# MotorBoardPrototyp4_ptcfuse.net
KiCad netlist of a schematic drawn in EAGLE
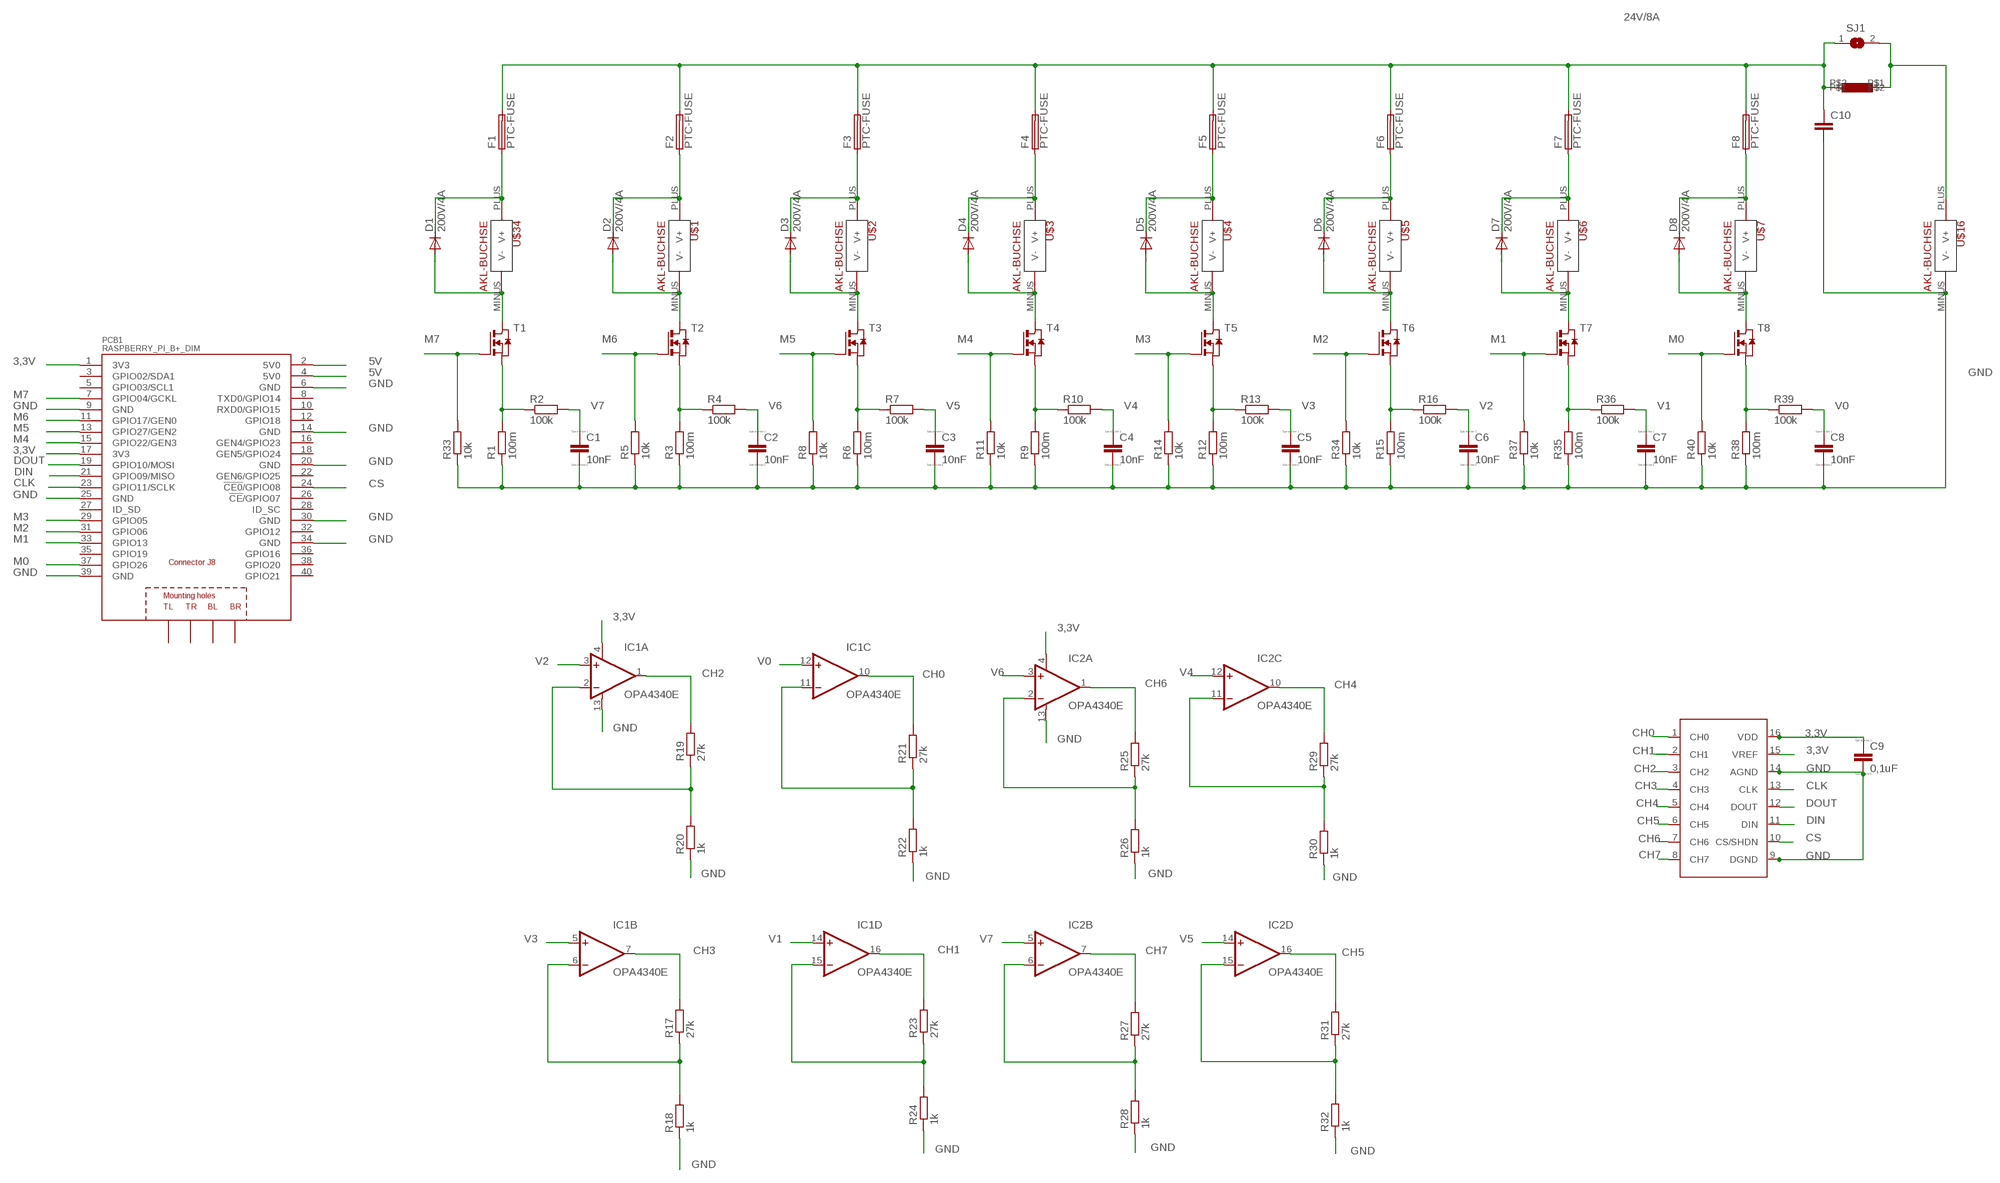
[diagram p0: schematic, sheet 1]

(export (version "E")
  (design (tool "Eeschema 10.0.6"))
  (components
    (comp (ref "C1")
      (value "10nF")
      (footprint "eagle-import:C0805")
      (libsource (lib "eagle-import") (part "C"))
    )
    (comp (ref "C2")
      (value "10nF")
      (footprint "eagle-import:C0805")
      (libsource (lib "eagle-import") (part "C"))
    )
    (comp (ref "C3")
      (value "10nF")
      (footprint "eagle-import:C0805")
      (libsource (lib "eagle-import") (part "C"))
    )
    (comp (ref "C4")
      (value "10nF")
      (footprint "eagle-import:C0805")
      (libsource (lib "eagle-import") (part "C"))
    )
    (comp (ref "C5")
      (value "10nF")
      (footprint "eagle-import:C0805")
      (libsource (lib "eagle-import") (part "C"))
    )
    (comp (ref "C6")
      (value "10nF")
      (footprint "eagle-import:C0805")
      (libsource (lib "eagle-import") (part "C"))
    )
    (comp (ref "C7")
      (value "10nF")
      (footprint "eagle-import:C0805")
      (libsource (lib "eagle-import") (part "C"))
    )
    (comp (ref "C8")
      (value "10nF")
      (footprint "eagle-import:C0805")
      (libsource (lib "eagle-import") (part "C"))
    )
    (comp (ref "C9")
      (value "0,1uF")
      (footprint "eagle-import:C0805")
      (libsource (lib "eagle-import") (part "C"))
    )
    (comp (ref "C10")
      (value "C-EUC1812")
      (footprint "eagle-import:C1812")
      (libsource (lib "eagle-import") (part "C-EUC1812"))
    )
    (comp (ref "D1")
      (value "200V/4A")
      (footprint "eagle-import:DO214AA")
      (libsource (lib "eagle-import") (part "DIODE-DO214AA"))
    )
    (comp (ref "D2")
      (value "200V/4A")
      (footprint "eagle-import:DO214AA")
      (libsource (lib "eagle-import") (part "DIODE-DO214AA"))
    )
    (comp (ref "D3")
      (value "200V/4A")
      (footprint "eagle-import:DO214AA")
      (libsource (lib "eagle-import") (part "DIODE-DO214AA"))
    )
    (comp (ref "D4")
      (value "200V/4A")
      (footprint "eagle-import:DO214AA")
      (libsource (lib "eagle-import") (part "DIODE-DO214AA"))
    )
    (comp (ref "D5")
      (value "200V/4A")
      (footprint "eagle-import:DO214AA")
      (libsource (lib "eagle-import") (part "DIODE-DO214AA"))
    )
    (comp (ref "D6")
      (value "200V/4A")
      (footprint "eagle-import:DO214AA")
      (libsource (lib "eagle-import") (part "DIODE-DO214AA"))
    )
    (comp (ref "D7")
      (value "200V/4A")
      (footprint "eagle-import:DO214AA")
      (libsource (lib "eagle-import") (part "DIODE-DO214AA"))
    )
    (comp (ref "D8")
      (value "200V/4A")
      (footprint "eagle-import:DO214AA")
      (libsource (lib "eagle-import") (part "DIODE-DO214AA"))
    )
    (comp (ref "F1")
      (value "PTC-FUSE")
      (footprint "eagle-import:SMDF050")
      (libsource (lib "eagle-import") (part "PTC-FUSE"))
    )
    (comp (ref "F2")
      (value "PTC-FUSE")
      (footprint "eagle-import:SMDF050")
      (libsource (lib "eagle-import") (part "PTC-FUSE"))
    )
    (comp (ref "F3")
      (value "PTC-FUSE")
      (footprint "eagle-import:SMDF050")
      (libsource (lib "eagle-import") (part "PTC-FUSE"))
    )
    (comp (ref "F4")
      (value "PTC-FUSE")
      (footprint "eagle-import:SMDF050")
      (libsource (lib "eagle-import") (part "PTC-FUSE"))
    )
    (comp (ref "F5")
      (value "PTC-FUSE")
      (footprint "eagle-import:SMDF050")
      (libsource (lib "eagle-import") (part "PTC-FUSE"))
    )
    (comp (ref "F6")
      (value "PTC-FUSE")
      (footprint "eagle-import:SMDF050")
      (libsource (lib "eagle-import") (part "PTC-FUSE"))
    )
    (comp (ref "F7")
      (value "PTC-FUSE")
      (footprint "eagle-import:SMDF050")
      (libsource (lib "eagle-import") (part "PTC-FUSE"))
    )
    (comp (ref "F8")
      (value "PTC-FUSE")
      (footprint "eagle-import:SMDF050")
      (libsource (lib "eagle-import") (part "PTC-FUSE"))
    )
    (comp (ref "IC1")
      (value "OPA4340E")
      (footprint "eagle-import:SSOP16BU")
      (fields (field (name "MPN") "OPA4340EA/250G4"))
      (libsource (lib "eagle-import") (part "OPA4340E"))
    )
    (comp (ref "IC2")
      (value "OPA4340E")
      (footprint "eagle-import:SSOP16BU")
      (fields (field (name "MPN") "OPA4340EA/250G4"))
      (libsource (lib "eagle-import") (part "OPA4340E"))
    )
    (comp (ref "L1")
      (value "MPI4040")
      (footprint "eagle-import:4040")
      (libsource (lib "eagle-import") (part "MPI4040"))
    )
    (comp (ref "PCB1")
      (value "RASPBERRY_PI_B+_DIM")
      (footprint "eagle-import:RASPBERRY_PI_BPLUS_DIM")
      (libsource (lib "eagle-import") (part "RASPBERRY_PI_B+_DIM"))
    )
    (comp (ref "R1")
      (value "100m")
      (footprint "eagle-import:R0805")
      (libsource (lib "eagle-import") (part "R-EU_R0805"))
    )
    (comp (ref "R2")
      (value "100k")
      (footprint "eagle-import:R0805")
      (libsource (lib "eagle-import") (part "R-EU_R0805"))
    )
    (comp (ref "R3")
      (value "100m")
      (footprint "eagle-import:R0805")
      (libsource (lib "eagle-import") (part "R-EU_R0805"))
    )
    (comp (ref "R4")
      (value "100k")
      (footprint "eagle-import:R0805")
      (libsource (lib "eagle-import") (part "R-EU_R0805"))
    )
    (comp (ref "R5")
      (value "10k")
      (footprint "eagle-import:R0805")
      (libsource (lib "eagle-import") (part "R-EU_R0805"))
    )
    (comp (ref "R6")
      (value "100m")
      (footprint "eagle-import:R0805")
      (libsource (lib "eagle-import") (part "R-EU_R0805"))
    )
    (comp (ref "R7")
      (value "100k")
      (footprint "eagle-import:R0805")
      (libsource (lib "eagle-import") (part "R-EU_R0805"))
    )
    (comp (ref "R8")
      (value "10k")
      (footprint "eagle-import:R0805")
      (libsource (lib "eagle-import") (part "R-EU_R0805"))
    )
    (comp (ref "R9")
      (value "100m")
      (footprint "eagle-import:R0805")
      (libsource (lib "eagle-import") (part "R-EU_R0805"))
    )
    (comp (ref "R10")
      (value "100k")
      (footprint "eagle-import:R0805")
      (libsource (lib "eagle-import") (part "R-EU_R0805"))
    )
    (comp (ref "R11")
      (value "10k")
      (footprint "eagle-import:R0805")
      (libsource (lib "eagle-import") (part "R-EU_R0805"))
    )
    (comp (ref "R12")
      (value "100m")
      (footprint "eagle-import:R0805")
      (libsource (lib "eagle-import") (part "R-EU_R0805"))
    )
    (comp (ref "R13")
      (value "100k")
      (footprint "eagle-import:R0805")
      (libsource (lib "eagle-import") (part "R-EU_R0805"))
    )
    (comp (ref "R14")
      (value "10k")
      (footprint "eagle-import:R0805")
      (libsource (lib "eagle-import") (part "R-EU_R0805"))
    )
    (comp (ref "R15")
      (value "100m")
      (footprint "eagle-import:R0805")
      (libsource (lib "eagle-import") (part "R-EU_R0805"))
    )
    (comp (ref "R16")
      (value "100k")
      (footprint "eagle-import:R0805")
      (libsource (lib "eagle-import") (part "R-EU_R0805"))
    )
    (comp (ref "R17")
      (value "27k")
      (footprint "eagle-import:R0805")
      (libsource (lib "eagle-import") (part "R-EU_R0805"))
    )
    (comp (ref "R18")
      (value "1k")
      (footprint "eagle-import:R0805")
      (libsource (lib "eagle-import") (part "R-EU_R0805"))
    )
    (comp (ref "R19")
      (value "27k")
      (footprint "eagle-import:R0805")
      (libsource (lib "eagle-import") (part "R-EU_R0805"))
    )
    (comp (ref "R20")
      (value "1k")
      (footprint "eagle-import:R0805")
      (libsource (lib "eagle-import") (part "R-EU_R0805"))
    )
    (comp (ref "R21")
      (value "27k")
      (footprint "eagle-import:R0805")
      (libsource (lib "eagle-import") (part "R-EU_R0805"))
    )
    (comp (ref "R22")
      (value "1k")
      (footprint "eagle-import:R0805")
      (libsource (lib "eagle-import") (part "R-EU_R0805"))
    )
    (comp (ref "R23")
      (value "27k")
      (footprint "eagle-import:R0805")
      (libsource (lib "eagle-import") (part "R-EU_R0805"))
    )
    (comp (ref "R24")
      (value "1k")
      (footprint "eagle-import:R0805")
      (libsource (lib "eagle-import") (part "R-EU_R0805"))
    )
    (comp (ref "R25")
      (value "27k")
      (footprint "eagle-import:R0805")
      (libsource (lib "eagle-import") (part "R-EU_R0805"))
    )
    (comp (ref "R26")
      (value "1k")
      (footprint "eagle-import:R0805")
      (libsource (lib "eagle-import") (part "R-EU_R0805"))
    )
    (comp (ref "R27")
      (value "27k")
      (footprint "eagle-import:R0805")
      (libsource (lib "eagle-import") (part "R-EU_R0805"))
    )
    (comp (ref "R28")
      (value "1k")
      (footprint "eagle-import:R0805")
      (libsource (lib "eagle-import") (part "R-EU_R0805"))
    )
    (comp (ref "R29")
      (value "27k")
      (footprint "eagle-import:R0805")
      (libsource (lib "eagle-import") (part "R-EU_R0805"))
    )
    (comp (ref "R30")
      (value "1k")
      (footprint "eagle-import:R0805")
      (libsource (lib "eagle-import") (part "R-EU_R0805"))
    )
    (comp (ref "R31")
      (value "27k")
      (footprint "eagle-import:R0805")
      (libsource (lib "eagle-import") (part "R-EU_R0805"))
    )
    (comp (ref "R32")
      (value "1k")
      (footprint "eagle-import:R0805")
      (libsource (lib "eagle-import") (part "R-EU_R0805"))
    )
    (comp (ref "R33")
      (value "10k")
      (footprint "eagle-import:R0805")
      (libsource (lib "eagle-import") (part "R-EU_R0805"))
    )
    (comp (ref "R34")
      (value "10k")
      (footprint "eagle-import:R0805")
      (libsource (lib "eagle-import") (part "R-EU_R0805"))
    )
    (comp (ref "R35")
      (value "100m")
      (footprint "eagle-import:R0805")
      (libsource (lib "eagle-import") (part "R-EU_R0805"))
    )
    (comp (ref "R36")
      (value "100k")
      (footprint "eagle-import:R0805")
      (libsource (lib "eagle-import") (part "R-EU_R0805"))
    )
    (comp (ref "R37")
      (value "10k")
      (footprint "eagle-import:R0805")
      (libsource (lib "eagle-import") (part "R-EU_R0805"))
    )
    (comp (ref "R38")
      (value "100m")
      (footprint "eagle-import:R0805")
      (libsource (lib "eagle-import") (part "R-EU_R0805"))
    )
    (comp (ref "R39")
      (value "100k")
      (footprint "eagle-import:R0805")
      (libsource (lib "eagle-import") (part "R-EU_R0805"))
    )
    (comp (ref "R40")
      (value "10k")
      (footprint "eagle-import:R0805")
      (libsource (lib "eagle-import") (part "R-EU_R0805"))
    )
    (comp (ref "SJ1") (value "SJ") (footprint "eagle-import:SJ") (libsource (lib "eagle-import") (part "SJ")))
    (comp (ref "T1")
      (value "NMOSSOT23")
      (footprint "eagle-import:SOT-23")
      (libsource (lib "eagle-import") (part "NMOSSOT23"))
    )
    (comp (ref "T2")
      (value "NMOSSOT23")
      (footprint "eagle-import:SOT-23")
      (libsource (lib "eagle-import") (part "NMOSSOT23"))
    )
    (comp (ref "T3")
      (value "NMOSSOT23")
      (footprint "eagle-import:SOT-23")
      (libsource (lib "eagle-import") (part "NMOSSOT23"))
    )
    (comp (ref "T4")
      (value "NMOSSOT23")
      (footprint "eagle-import:SOT-23")
      (libsource (lib "eagle-import") (part "NMOSSOT23"))
    )
    (comp (ref "T5")
      (value "NMOSSOT23")
      (footprint "eagle-import:SOT-23")
      (libsource (lib "eagle-import") (part "NMOSSOT23"))
    )
    (comp (ref "T6")
      (value "NMOSSOT23")
      (footprint "eagle-import:SOT-23")
      (libsource (lib "eagle-import") (part "NMOSSOT23"))
    )
    (comp (ref "T7")
      (value "NMOSSOT23")
      (footprint "eagle-import:SOT-23")
      (libsource (lib "eagle-import") (part "NMOSSOT23"))
    )
    (comp (ref "T8")
      (value "NMOSSOT23")
      (footprint "eagle-import:SOT-23")
      (libsource (lib "eagle-import") (part "NMOSSOT23"))
    )
    (comp (ref "U$1")
      (value "AKL-BUCHSE")
      (footprint "eagle-import:AKL-BUCHSE")
      (libsource (lib "eagle-import") (part "AKL-BUCHSE"))
    )
    (comp (ref "U$2")
      (value "AKL-BUCHSE")
      (footprint "eagle-import:AKL-BUCHSE")
      (libsource (lib "eagle-import") (part "AKL-BUCHSE"))
    )
    (comp (ref "U$3")
      (value "AKL-BUCHSE")
      (footprint "eagle-import:AKL-BUCHSE")
      (libsource (lib "eagle-import") (part "AKL-BUCHSE"))
    )
    (comp (ref "U$4")
      (value "AKL-BUCHSE")
      (footprint "eagle-import:AKL-BUCHSE")
      (libsource (lib "eagle-import") (part "AKL-BUCHSE"))
    )
    (comp (ref "U$5")
      (value "AKL-BUCHSE")
      (footprint "eagle-import:AKL-BUCHSE")
      (libsource (lib "eagle-import") (part "AKL-BUCHSE"))
    )
    (comp (ref "U$6")
      (value "AKL-BUCHSE")
      (footprint "eagle-import:AKL-BUCHSE")
      (libsource (lib "eagle-import") (part "AKL-BUCHSE"))
    )
    (comp (ref "U$7")
      (value "AKL-BUCHSE")
      (footprint "eagle-import:AKL-BUCHSE")
      (libsource (lib "eagle-import") (part "AKL-BUCHSE"))
    )
    (comp (ref "U$16")
      (value "AKL-BUCHSE")
      (footprint "eagle-import:AKL-BUCHSE")
      (libsource (lib "eagle-import") (part "AKL-BUCHSE"))
    )
    (comp (ref "U$34")
      (value "AKL-BUCHSE")
      (footprint "eagle-import:AKL-BUCHSE")
      (libsource (lib "eagle-import") (part "AKL-BUCHSE"))
    )
    (comp (ref "U$58")
      (value "MCP3008SO16")
      (footprint "eagle-import:SO16")
      (libsource (lib "eagle-import") (part "MCP3008SO16"))
    )
  )
  (nets
    (net (code "1") (name "/3,3V") (class "Default")
      (node (ref "C9") (pin "1") (pinfunction "1_1") (pintype "passive"))
      (node (ref "IC1") (pin "4") (pinfunction "V+_4") (pintype "power_in"))
      (node (ref "IC2") (pin "4") (pinfunction "V+_4") (pintype "power_in"))
      (node (ref "PCB1") (pin "1") (pinfunction "3V3_1") (pintype "power_in"))
      (node (ref "PCB1") (pin "17") (pinfunction "3V3_17") (pintype "power_in"))
      (node (ref "U$58") (pin "15") (pinfunction "VREF_15") (pintype "bidirectional"))
      (node (ref "U$58") (pin "16") (pinfunction "VDD_16") (pintype "bidirectional"))
    )
    (net (code "2") (name "/5V") (class "Default")
      (node (ref "PCB1") (pin "2") (pinfunction "5V0_2") (pintype "power_in"))
      (node (ref "PCB1") (pin "4") (pinfunction "5V0_4") (pintype "power_in"))
    )
    (net (code "3") (name "/24V{slash}8A") (class "Default")
      (node (ref "C10") (pin "1") (pinfunction "1_1") (pintype "passive"))
      (node (ref "F1") (pin "P$2") (pinfunction "2_P$2") (pintype "passive"))
      (node (ref "F2") (pin "P$2") (pinfunction "2_P$2") (pintype "passive"))
      (node (ref "F3") (pin "P$2") (pinfunction "2_P$2") (pintype "passive"))
      (node (ref "F4") (pin "P$2") (pinfunction "2_P$2") (pintype "passive"))
      (node (ref "F5") (pin "P$2") (pinfunction "2_P$2") (pintype "passive"))
      (node (ref "F6") (pin "P$2") (pinfunction "2_P$2") (pintype "passive"))
      (node (ref "F7") (pin "P$2") (pinfunction "2_P$2") (pintype "passive"))
      (node (ref "F8") (pin "P$2") (pinfunction "2_P$2") (pintype "passive"))
      (node (ref "L1") (pin "P$2") (pinfunction "P$2_P$2") (pintype "bidirectional"))
      (node (ref "SJ1") (pin "1") (pinfunction "1_1") (pintype "passive"))
    )
    (net (code "4") (name "/CH0") (class "Default")
      (node (ref "IC1") (pin "10") (pinfunction "OUT_10") (pintype "output"))
      (node (ref "R21") (pin "2") (pinfunction "2_2") (pintype "passive"))
      (node (ref "U$58") (pin "1") (pinfunction "CH0_1") (pintype "bidirectional"))
    )
    (net (code "5") (name "/CH1") (class "Default")
      (node (ref "IC1") (pin "16") (pinfunction "OUT_16") (pintype "output"))
      (node (ref "R23") (pin "2") (pinfunction "2_2") (pintype "passive"))
      (node (ref "U$58") (pin "2") (pinfunction "CH1_2") (pintype "bidirectional"))
    )
    (net (code "6") (name "/CH2") (class "Default")
      (node (ref "IC1") (pin "1") (pinfunction "OUT_1") (pintype "output"))
      (node (ref "R19") (pin "2") (pinfunction "2_2") (pintype "passive"))
      (node (ref "U$58") (pin "3") (pinfunction "CH2_3") (pintype "bidirectional"))
    )
    (net (code "7") (name "/CH3") (class "Default")
      (node (ref "IC1") (pin "7") (pinfunction "OUT_7") (pintype "output"))
      (node (ref "R17") (pin "2") (pinfunction "2_2") (pintype "passive"))
      (node (ref "U$58") (pin "4") (pinfunction "CH3_4") (pintype "bidirectional"))
    )
    (net (code "8") (name "/CH4") (class "Default")
      (node (ref "IC2") (pin "10") (pinfunction "OUT_10") (pintype "output"))
      (node (ref "R29") (pin "2") (pinfunction "2_2") (pintype "passive"))
      (node (ref "U$58") (pin "5") (pinfunction "CH4_5") (pintype "bidirectional"))
    )
    (net (code "9") (name "/CH5") (class "Default")
      (node (ref "IC2") (pin "16") (pinfunction "OUT_16") (pintype "output"))
      (node (ref "R31") (pin "2") (pinfunction "2_2") (pintype "passive"))
      (node (ref "U$58") (pin "6") (pinfunction "CH5_6") (pintype "bidirectional"))
    )
    (net (code "10") (name "/CH6") (class "Default")
      (node (ref "IC2") (pin "1") (pinfunction "OUT_1") (pintype "output"))
      (node (ref "R25") (pin "2") (pinfunction "2_2") (pintype "passive"))
      (node (ref "U$58") (pin "7") (pinfunction "CH6_7") (pintype "bidirectional"))
    )
    (net (code "11") (name "/CH7") (class "Default")
      (node (ref "IC2") (pin "7") (pinfunction "OUT_7") (pintype "output"))
      (node (ref "R27") (pin "2") (pinfunction "2_2") (pintype "passive"))
      (node (ref "U$58") (pin "8") (pinfunction "CH7_8") (pintype "bidirectional"))
    )
    (net (code "12") (name "/CLK") (class "Default")
      (node (ref "PCB1") (pin "23") (pinfunction "GPIO11/SCLK_23") (pintype "bidirectional"))
      (node (ref "U$58") (pin "13") (pinfunction "CLK_13") (pintype "bidirectional"))
    )
    (net (code "13") (name "/CS") (class "Default")
      (node (ref "PCB1") (pin "24") (pinfunction "~{CE0}/GPIO08_24") (pintype "bidirectional"))
      (node (ref "U$58") (pin "10") (pinfunction "CS/SHDN_10") (pintype "bidirectional"))
    )
    (net (code "14") (name "/DIN") (class "Default")
      (node (ref "PCB1") (pin "21") (pinfunction "GPIO09/MISO_21") (pintype "bidirectional"))
      (node (ref "U$58") (pin "11") (pinfunction "DIN_11") (pintype "bidirectional"))
    )
    (net (code "15") (name "/DOUT") (class "Default")
      (node (ref "PCB1") (pin "19") (pinfunction "GPIO10/MOSI_19") (pintype "bidirectional"))
      (node (ref "U$58") (pin "12") (pinfunction "DOUT_12") (pintype "bidirectional"))
    )
    (net (code "16") (name "/GND") (class "Default")
      (node (ref "C1") (pin "2") (pinfunction "2_2") (pintype "passive"))
      (node (ref "C10") (pin "2") (pinfunction "2_2") (pintype "passive"))
      (node (ref "C2") (pin "2") (pinfunction "2_2") (pintype "passive"))
      (node (ref "C3") (pin "2") (pinfunction "2_2") (pintype "passive"))
      (node (ref "C4") (pin "2") (pinfunction "2_2") (pintype "passive"))
      (node (ref "C5") (pin "2") (pinfunction "2_2") (pintype "passive"))
      (node (ref "C6") (pin "2") (pinfunction "2_2") (pintype "passive"))
      (node (ref "C7") (pin "2") (pinfunction "2_2") (pintype "passive"))
      (node (ref "C8") (pin "2") (pinfunction "2_2") (pintype "passive"))
      (node (ref "C9") (pin "2") (pinfunction "2_2") (pintype "passive"))
      (node (ref "IC1") (pin "13") (pinfunction "V-_13") (pintype "power_in"))
      (node (ref "IC2") (pin "13") (pinfunction "V-_13") (pintype "power_in"))
      (node (ref "PCB1") (pin "14") (pinfunction "GND_14") (pintype "power_in"))
      (node (ref "PCB1") (pin "20") (pinfunction "GND_20") (pintype "power_in"))
      (node (ref "PCB1") (pin "25") (pinfunction "GND_25") (pintype "power_in"))
      (node (ref "PCB1") (pin "30") (pinfunction "GND_30") (pintype "power_in"))
      (node (ref "PCB1") (pin "34") (pinfunction "GND_34") (pintype "power_in"))
      (node (ref "PCB1") (pin "39") (pinfunction "GND_39") (pintype "power_in"))
      (node (ref "PCB1") (pin "6") (pinfunction "GND_6") (pintype "power_in"))
      (node (ref "PCB1") (pin "9") (pinfunction "GND_9") (pintype "power_in"))
      (node (ref "R1") (pin "1") (pinfunction "1_1") (pintype "passive"))
      (node (ref "R11") (pin "1") (pinfunction "1_1") (pintype "passive"))
      (node (ref "R12") (pin "1") (pinfunction "1_1") (pintype "passive"))
      (node (ref "R14") (pin "1") (pinfunction "1_1") (pintype "passive"))
      (node (ref "R15") (pin "1") (pinfunction "1_1") (pintype "passive"))
      (node (ref "R18") (pin "1") (pinfunction "1_1") (pintype "passive"))
      (node (ref "R20") (pin "1") (pinfunction "1_1") (pintype "passive"))
      (node (ref "R22") (pin "1") (pinfunction "1_1") (pintype "passive"))
      (node (ref "R24") (pin "1") (pinfunction "1_1") (pintype "passive"))
      (node (ref "R26") (pin "1") (pinfunction "1_1") (pintype "passive"))
      (node (ref "R28") (pin "1") (pinfunction "1_1") (pintype "passive"))
      (node (ref "R3") (pin "1") (pinfunction "1_1") (pintype "passive"))
      (node (ref "R30") (pin "1") (pinfunction "1_1") (pintype "passive"))
      (node (ref "R32") (pin "1") (pinfunction "1_1") (pintype "passive"))
      (node (ref "R33") (pin "1") (pinfunction "1_1") (pintype "passive"))
      (node (ref "R34") (pin "1") (pinfunction "1_1") (pintype "passive"))
      (node (ref "R35") (pin "1") (pinfunction "1_1") (pintype "passive"))
      (node (ref "R37") (pin "1") (pinfunction "1_1") (pintype "passive"))
      (node (ref "R38") (pin "1") (pinfunction "1_1") (pintype "passive"))
      (node (ref "R40") (pin "1") (pinfunction "1_1") (pintype "passive"))
      (node (ref "R5") (pin "1") (pinfunction "1_1") (pintype "passive"))
      (node (ref "R6") (pin "1") (pinfunction "1_1") (pintype "passive"))
      (node (ref "R8") (pin "1") (pinfunction "1_1") (pintype "passive"))
      (node (ref "R9") (pin "1") (pinfunction "1_1") (pintype "passive"))
      (node (ref "U$16") (pin "MINUS") (pinfunction "V-_MINUS") (pintype "bidirectional"))
      (node (ref "U$58") (pin "14") (pinfunction "AGND_14") (pintype "bidirectional"))
      (node (ref "U$58") (pin "9") (pinfunction "DGND_9") (pintype "bidirectional"))
    )
    (net (code "17") (name "/M0") (class "Default")
      (node (ref "PCB1") (pin "37") (pinfunction "GPIO26_37") (pintype "bidirectional"))
      (node (ref "R40") (pin "2") (pinfunction "2_2") (pintype "passive"))
      (node (ref "T8") (pin "3") (pinfunction "G_3") (pintype "passive"))
    )
    (net (code "18") (name "/M1") (class "Default")
      (node (ref "PCB1") (pin "33") (pinfunction "GPIO13_33") (pintype "bidirectional"))
      (node (ref "R37") (pin "2") (pinfunction "2_2") (pintype "passive"))
      (node (ref "T7") (pin "3") (pinfunction "G_3") (pintype "passive"))
    )
    (net (code "19") (name "/M2") (class "Default")
      (node (ref "PCB1") (pin "31") (pinfunction "GPIO06_31") (pintype "bidirectional"))
      (node (ref "R34") (pin "2") (pinfunction "2_2") (pintype "passive"))
      (node (ref "T6") (pin "3") (pinfunction "G_3") (pintype "passive"))
    )
    (net (code "20") (name "/M3") (class "Default")
      (node (ref "PCB1") (pin "29") (pinfunction "GPIO05_29") (pintype "bidirectional"))
      (node (ref "R14") (pin "2") (pinfunction "2_2") (pintype "passive"))
      (node (ref "T5") (pin "3") (pinfunction "G_3") (pintype "passive"))
    )
    (net (code "21") (name "/M4") (class "Default")
      (node (ref "PCB1") (pin "15") (pinfunction "GPIO22/GEN3_15") (pintype "bidirectional"))
      (node (ref "R11") (pin "2") (pinfunction "2_2") (pintype "passive"))
      (node (ref "T4") (pin "3") (pinfunction "G_3") (pintype "passive"))
    )
    (net (code "22") (name "/M5") (class "Default")
      (node (ref "PCB1") (pin "13") (pinfunction "GPIO27/GEN2_13") (pintype "bidirectional"))
      (node (ref "R8") (pin "2") (pinfunction "2_2") (pintype "passive"))
      (node (ref "T3") (pin "3") (pinfunction "G_3") (pintype "passive"))
    )
    (net (code "23") (name "/M6") (class "Default")
      (node (ref "PCB1") (pin "11") (pinfunction "GPIO17/GEN0_11") (pintype "bidirectional"))
      (node (ref "R5") (pin "2") (pinfunction "2_2") (pintype "passive"))
      (node (ref "T2") (pin "3") (pinfunction "G_3") (pintype "passive"))
    )
    (net (code "24") (name "/M7") (class "Default")
      (node (ref "PCB1") (pin "7") (pinfunction "GPIO04/GCKL_7") (pintype "bidirectional"))
      (node (ref "R33") (pin "2") (pinfunction "2_2") (pintype "passive"))
      (node (ref "T1") (pin "3") (pinfunction "G_3") (pintype "passive"))
    )
    (net (code "25") (name "/V0") (class "Default")
      (node (ref "C8") (pin "1") (pinfunction "1_1") (pintype "passive"))
      (node (ref "IC1") (pin "12") (pinfunction "+IN_12") (pintype "input"))
      (node (ref "R39") (pin "2") (pinfunction "2_2") (pintype "passive"))
    )
    (net (code "26") (name "/V1") (class "Default")
      (node (ref "C7") (pin "1") (pinfunction "1_1") (pintype "passive"))
      (node (ref "IC1") (pin "14") (pinfunction "+IN_14") (pintype "input"))
      (node (ref "R36") (pin "2") (pinfunction "2_2") (pintype "passive"))
    )
    (net (code "27") (name "/V2") (class "Default")
      (node (ref "C6") (pin "1") (pinfunction "1_1") (pintype "passive"))
      (node (ref "IC1") (pin "3") (pinfunction "+IN_3") (pintype "input"))
      (node (ref "R16") (pin "2") (pinfunction "2_2") (pintype "passive"))
    )
    (net (code "28") (name "/V3") (class "Default")
      (node (ref "C5") (pin "1") (pinfunction "1_1") (pintype "passive"))
      (node (ref "IC1") (pin "5") (pinfunction "+IN_5") (pintype "input"))
      (node (ref "R13") (pin "2") (pinfunction "2_2") (pintype "passive"))
    )
    (net (code "29") (name "/V4") (class "Default")
      (node (ref "C4") (pin "1") (pinfunction "1_1") (pintype "passive"))
      (node (ref "IC2") (pin "12") (pinfunction "+IN_12") (pintype "input"))
      (node (ref "R10") (pin "2") (pinfunction "2_2") (pintype "passive"))
    )
    (net (code "30") (name "/V5") (class "Default")
      (node (ref "C3") (pin "1") (pinfunction "1_1") (pintype "passive"))
      (node (ref "IC2") (pin "14") (pinfunction "+IN_14") (pintype "input"))
      (node (ref "R7") (pin "2") (pinfunction "2_2") (pintype "passive"))
    )
    (net (code "31") (name "/V6") (class "Default")
      (node (ref "C2") (pin "1") (pinfunction "1_1") (pintype "passive"))
      (node (ref "IC2") (pin "3") (pinfunction "+IN_3") (pintype "input"))
      (node (ref "R4") (pin "2") (pinfunction "2_2") (pintype "passive"))
    )
    (net (code "32") (name "/V7") (class "Default")
      (node (ref "C1") (pin "1") (pinfunction "1_1") (pintype "passive"))
      (node (ref "IC2") (pin "5") (pinfunction "+IN_5") (pintype "input"))
      (node (ref "R2") (pin "2") (pinfunction "2_2") (pintype "passive"))
    )
    (net (code "33") (name "Net-(F1-1)") (class "Default")
      (node (ref "D1") (pin "C") (pinfunction "C_C") (pintype "passive"))
      (node (ref "F1") (pin "P$1") (pinfunction "1_P$1") (pintype "passive"))
      (node (ref "U$34") (pin "PLUS") (pinfunction "V+_PLUS") (pintype "bidirectional"))
    )
    (net (code "34") (name "Net-(F2-1)") (class "Default")
      (node (ref "D2") (pin "C") (pinfunction "C_C") (pintype "passive"))
      (node (ref "F2") (pin "P$1") (pinfunction "1_P$1") (pintype "passive"))
      (node (ref "U$1") (pin "PLUS") (pinfunction "V+_PLUS") (pintype "bidirectional"))
    )
    (net (code "35") (name "Net-(F3-1)") (class "Default")
      (node (ref "D3") (pin "C") (pinfunction "C_C") (pintype "passive"))
      (node (ref "F3") (pin "P$1") (pinfunction "1_P$1") (pintype "passive"))
      (node (ref "U$2") (pin "PLUS") (pinfunction "V+_PLUS") (pintype "bidirectional"))
    )
    (net (code "36") (name "Net-(F4-1)") (class "Default")
      (node (ref "D4") (pin "C") (pinfunction "C_C") (pintype "passive"))
      (node (ref "F4") (pin "P$1") (pinfunction "1_P$1") (pintype "passive"))
      (node (ref "U$3") (pin "PLUS") (pinfunction "V+_PLUS") (pintype "bidirectional"))
    )
    (net (code "37") (name "Net-(F5-1)") (class "Default")
      (node (ref "D5") (pin "C") (pinfunction "C_C") (pintype "passive"))
      (node (ref "F5") (pin "P$1") (pinfunction "1_P$1") (pintype "passive"))
      (node (ref "U$4") (pin "PLUS") (pinfunction "V+_PLUS") (pintype "bidirectional"))
    )
    (net (code "38") (name "Net-(F6-1)") (class "Default")
      (node (ref "D6") (pin "C") (pinfunction "C_C") (pintype "passive"))
      (node (ref "F6") (pin "P$1") (pinfunction "1_P$1") (pintype "passive"))
      (node (ref "U$5") (pin "PLUS") (pinfunction "V+_PLUS") (pintype "bidirectional"))
    )
    (net (code "39") (name "Net-(F7-1)") (class "Default")
      (node (ref "D7") (pin "C") (pinfunction "C_C") (pintype "passive"))
      (node (ref "F7") (pin "P$1") (pinfunction "1_P$1") (pintype "passive"))
      (node (ref "U$6") (pin "PLUS") (pinfunction "V+_PLUS") (pintype "bidirectional"))
    )
    (net (code "40") (name "Net-(F8-1)") (class "Default")
      (node (ref "D8") (pin "C") (pinfunction "C_C") (pintype "passive"))
      (node (ref "F8") (pin "P$1") (pinfunction "1_P$1") (pintype "passive"))
      (node (ref "U$7") (pin "PLUS") (pinfunction "V+_PLUS") (pintype "bidirectional"))
    )
    (net (code "41") (name "Net-(IC1A--IN)") (class "Default")
      (node (ref "IC1") (pin "2") (pinfunction "-IN_2") (pintype "input"))
      (node (ref "R19") (pin "1") (pinfunction "1_1") (pintype "passive"))
      (node (ref "R20") (pin "2") (pinfunction "2_2") (pintype "passive"))
    )
    (net (code "42") (name "Net-(IC1B--IN)") (class "Default")
      (node (ref "IC1") (pin "6") (pinfunction "-IN_6") (pintype "input"))
      (node (ref "R17") (pin "1") (pinfunction "1_1") (pintype "passive"))
      (node (ref "R18") (pin "2") (pinfunction "2_2") (pintype "passive"))
    )
    (net (code "43") (name "Net-(IC1C--IN)") (class "Default")
      (node (ref "IC1") (pin "11") (pinfunction "-IN_11") (pintype "input"))
      (node (ref "R21") (pin "1") (pinfunction "1_1") (pintype "passive"))
      (node (ref "R22") (pin "2") (pinfunction "2_2") (pintype "passive"))
    )
    (net (code "44") (name "Net-(IC1D--IN)") (class "Default")
      (node (ref "IC1") (pin "15") (pinfunction "-IN_15") (pintype "input"))
      (node (ref "R23") (pin "1") (pinfunction "1_1") (pintype "passive"))
      (node (ref "R24") (pin "2") (pinfunction "2_2") (pintype "passive"))
    )
    (net (code "45") (name "Net-(IC2A--IN)") (class "Default")
      (node (ref "IC2") (pin "2") (pinfunction "-IN_2") (pintype "input"))
      (node (ref "R25") (pin "1") (pinfunction "1_1") (pintype "passive"))
      (node (ref "R26") (pin "2") (pinfunction "2_2") (pintype "passive"))
    )
    (net (code "46") (name "Net-(IC2B--IN)") (class "Default")
      (node (ref "IC2") (pin "6") (pinfunction "-IN_6") (pintype "input"))
      (node (ref "R27") (pin "1") (pinfunction "1_1") (pintype "passive"))
      (node (ref "R28") (pin "2") (pinfunction "2_2") (pintype "passive"))
    )
    (net (code "47") (name "Net-(IC2C--IN)") (class "Default")
      (node (ref "IC2") (pin "11") (pinfunction "-IN_11") (pintype "input"))
      (node (ref "R29") (pin "1") (pinfunction "1_1") (pintype "passive"))
      (node (ref "R30") (pin "2") (pinfunction "2_2") (pintype "passive"))
    )
    (net (code "48") (name "Net-(IC2D--IN)") (class "Default")
      (node (ref "IC2") (pin "15") (pinfunction "-IN_15") (pintype "input"))
      (node (ref "R31") (pin "1") (pinfunction "1_1") (pintype "passive"))
      (node (ref "R32") (pin "2") (pinfunction "2_2") (pintype "passive"))
    )
    (net (code "49") (name "Net-(T1-D)") (class "Default")
      (node (ref "D1") (pin "A") (pinfunction "A_A") (pintype "passive"))
      (node (ref "T1") (pin "1") (pinfunction "D_1") (pintype "passive"))
      (node (ref "U$34") (pin "MINUS") (pinfunction "V-_MINUS") (pintype "bidirectional"))
    )
    (net (code "50") (name "Net-(T1-S)") (class "Default")
      (node (ref "R1") (pin "2") (pinfunction "2_2") (pintype "passive"))
      (node (ref "R2") (pin "1") (pinfunction "1_1") (pintype "passive"))
      (node (ref "T1") (pin "2") (pinfunction "S_2") (pintype "passive"))
    )
    (net (code "51") (name "Net-(T2-D)") (class "Default")
      (node (ref "D2") (pin "A") (pinfunction "A_A") (pintype "passive"))
      (node (ref "T2") (pin "1") (pinfunction "D_1") (pintype "passive"))
      (node (ref "U$1") (pin "MINUS") (pinfunction "V-_MINUS") (pintype "bidirectional"))
    )
    (net (code "52") (name "Net-(T2-S)") (class "Default")
      (node (ref "R3") (pin "2") (pinfunction "2_2") (pintype "passive"))
      (node (ref "R4") (pin "1") (pinfunction "1_1") (pintype "passive"))
      (node (ref "T2") (pin "2") (pinfunction "S_2") (pintype "passive"))
    )
    (net (code "53") (name "Net-(T3-D)") (class "Default")
      (node (ref "D3") (pin "A") (pinfunction "A_A") (pintype "passive"))
      (node (ref "T3") (pin "1") (pinfunction "D_1") (pintype "passive"))
      (node (ref "U$2") (pin "MINUS") (pinfunction "V-_MINUS") (pintype "bidirectional"))
    )
    (net (code "54") (name "Net-(T3-S)") (class "Default")
      (node (ref "R6") (pin "2") (pinfunction "2_2") (pintype "passive"))
      (node (ref "R7") (pin "1") (pinfunction "1_1") (pintype "passive"))
      (node (ref "T3") (pin "2") (pinfunction "S_2") (pintype "passive"))
    )
    (net (code "55") (name "Net-(T4-D)") (class "Default")
      (node (ref "D4") (pin "A") (pinfunction "A_A") (pintype "passive"))
      (node (ref "T4") (pin "1") (pinfunction "D_1") (pintype "passive"))
      (node (ref "U$3") (pin "MINUS") (pinfunction "V-_MINUS") (pintype "bidirectional"))
    )
    (net (code "56") (name "Net-(T4-S)") (class "Default")
      (node (ref "R10") (pin "1") (pinfunction "1_1") (pintype "passive"))
      (node (ref "R9") (pin "2") (pinfunction "2_2") (pintype "passive"))
      (node (ref "T4") (pin "2") (pinfunction "S_2") (pintype "passive"))
    )
    (net (code "57") (name "Net-(T5-D)") (class "Default")
      (node (ref "D5") (pin "A") (pinfunction "A_A") (pintype "passive"))
      (node (ref "T5") (pin "1") (pinfunction "D_1") (pintype "passive"))
      (node (ref "U$4") (pin "MINUS") (pinfunction "V-_MINUS") (pintype "bidirectional"))
    )
    (net (code "58") (name "Net-(T5-S)") (class "Default")
      (node (ref "R12") (pin "2") (pinfunction "2_2") (pintype "passive"))
      (node (ref "R13") (pin "1") (pinfunction "1_1") (pintype "passive"))
      (node (ref "T5") (pin "2") (pinfunction "S_2") (pintype "passive"))
    )
    (net (code "59") (name "Net-(T6-D)") (class "Default")
      (node (ref "D6") (pin "A") (pinfunction "A_A") (pintype "passive"))
      (node (ref "T6") (pin "1") (pinfunction "D_1") (pintype "passive"))
      (node (ref "U$5") (pin "MINUS") (pinfunction "V-_MINUS") (pintype "bidirectional"))
    )
    (net (code "60") (name "Net-(T6-S)") (class "Default")
      (node (ref "R15") (pin "2") (pinfunction "2_2") (pintype "passive"))
      (node (ref "R16") (pin "1") (pinfunction "1_1") (pintype "passive"))
      (node (ref "T6") (pin "2") (pinfunction "S_2") (pintype "passive"))
    )
    (net (code "61") (name "Net-(T7-D)") (class "Default")
      (node (ref "D7") (pin "A") (pinfunction "A_A") (pintype "passive"))
      (node (ref "T7") (pin "1") (pinfunction "D_1") (pintype "passive"))
      (node (ref "U$6") (pin "MINUS") (pinfunction "V-_MINUS") (pintype "bidirectional"))
    )
    (net (code "62") (name "Net-(T7-S)") (class "Default")
      (node (ref "R35") (pin "2") (pinfunction "2_2") (pintype "passive"))
      (node (ref "R36") (pin "1") (pinfunction "1_1") (pintype "passive"))
      (node (ref "T7") (pin "2") (pinfunction "S_2") (pintype "passive"))
    )
    (net (code "63") (name "Net-(T8-D)") (class "Default")
      (node (ref "D8") (pin "A") (pinfunction "A_A") (pintype "passive"))
      (node (ref "T8") (pin "1") (pinfunction "D_1") (pintype "passive"))
      (node (ref "U$7") (pin "MINUS") (pinfunction "V-_MINUS") (pintype "bidirectional"))
    )
    (net (code "64") (name "Net-(T8-S)") (class "Default")
      (node (ref "R38") (pin "2") (pinfunction "2_2") (pintype "passive"))
      (node (ref "R39") (pin "1") (pinfunction "1_1") (pintype "passive"))
      (node (ref "T8") (pin "2") (pinfunction "S_2") (pintype "passive"))
    )
    (net (code "65") (name "Net-(U$16-V+)") (class "Default")
      (node (ref "L1") (pin "P$1") (pinfunction "P$1_P$1") (pintype "bidirectional"))
      (node (ref "SJ1") (pin "2") (pinfunction "2_2") (pintype "passive"))
      (node (ref "U$16") (pin "PLUS") (pinfunction "V+_PLUS") (pintype "bidirectional"))
    )
    (net (code "66") (name "unconnected-(PCB1-BL-PadPE_BL)") (class "Default")
      (node (ref "PCB1") (pin "PE_BL") (pinfunction "BL_PE_BL") (pintype "bidirectional"))
    )
    (net (code "67") (name "unconnected-(PCB1-BR-PadPE_BR)") (class "Default")
      (node (ref "PCB1") (pin "PE_BR") (pinfunction "BR_PE_BR") (pintype "bidirectional"))
    )
    (net (code "68") (name "unconnected-(PCB1-GEN4{slash}GPIO23-Pad16)") (class "Default")
      (node (ref "PCB1") (pin "16") (pinfunction "GEN4/GPIO23_16") (pintype "bidirectional"))
    )
    (net (code "69") (name "unconnected-(PCB1-GEN5{slash}GPIO24-Pad18)") (class "Default")
      (node (ref "PCB1") (pin "18") (pinfunction "GEN5/GPIO24_18") (pintype "bidirectional"))
    )
    (net (code "70") (name "unconnected-(PCB1-GEN6{slash}GPIO25-Pad22)") (class "Default")
      (node (ref "PCB1") (pin "22") (pinfunction "GEN6/GPIO25_22") (pintype "bidirectional"))
    )
    (net (code "71") (name "unconnected-(PCB1-GPIO02{slash}SDA1-Pad3)") (class "Default")
      (node (ref "PCB1") (pin "3") (pinfunction "GPIO02/SDA1_3") (pintype "bidirectional"))
    )
    (net (code "72") (name "unconnected-(PCB1-GPIO03{slash}SCL1-Pad5)") (class "Default")
      (node (ref "PCB1") (pin "5") (pinfunction "GPIO03/SCL1_5") (pintype "bidirectional"))
    )
    (net (code "73") (name "unconnected-(PCB1-GPIO12-Pad32)") (class "Default")
      (node (ref "PCB1") (pin "32") (pinfunction "GPIO12_32") (pintype "bidirectional"))
    )
    (net (code "74") (name "unconnected-(PCB1-GPIO16-Pad36)") (class "Default")
      (node (ref "PCB1") (pin "36") (pinfunction "GPIO16_36") (pintype "bidirectional"))
    )
    (net (code "75") (name "unconnected-(PCB1-GPIO18-Pad12)") (class "Default")
      (node (ref "PCB1") (pin "12") (pinfunction "GPIO18_12") (pintype "bidirectional"))
    )
    (net (code "76") (name "unconnected-(PCB1-GPIO19-Pad35)") (class "Default")
      (node (ref "PCB1") (pin "35") (pinfunction "GPIO19_35") (pintype "bidirectional"))
    )
    (net (code "77") (name "unconnected-(PCB1-GPIO20-Pad38)") (class "Default")
      (node (ref "PCB1") (pin "38") (pinfunction "GPIO20_38") (pintype "bidirectional"))
    )
    (net (code "78") (name "unconnected-(PCB1-GPIO21-Pad40)") (class "Default")
      (node (ref "PCB1") (pin "40") (pinfunction "GPIO21_40") (pintype "bidirectional"))
    )
    (net (code "79") (name "unconnected-(PCB1-ID_SC-Pad28)") (class "Default")
      (node (ref "PCB1") (pin "28") (pinfunction "ID_SC_28") (pintype "bidirectional"))
    )
    (net (code "80") (name "unconnected-(PCB1-ID_SD-Pad27)") (class "Default")
      (node (ref "PCB1") (pin "27") (pinfunction "ID_SD_27") (pintype "bidirectional"))
    )
    (net (code "81") (name "unconnected-(PCB1-RXD0{slash}GPIO15-Pad10)") (class "Default")
      (node (ref "PCB1") (pin "10") (pinfunction "RXD0/GPIO15_10") (pintype "bidirectional"))
    )
    (net (code "82") (name "unconnected-(PCB1-TL-PadPE_TL)") (class "Default")
      (node (ref "PCB1") (pin "PE_TL") (pinfunction "TL_PE_TL") (pintype "bidirectional"))
    )
    (net (code "83") (name "unconnected-(PCB1-TR-PadPE_TR)") (class "Default")
      (node (ref "PCB1") (pin "PE_TR") (pinfunction "TR_PE_TR") (pintype "bidirectional"))
    )
    (net (code "84") (name "unconnected-(PCB1-TXD0{slash}GPIO14-Pad8)") (class "Default")
      (node (ref "PCB1") (pin "8") (pinfunction "TXD0/GPIO14_8") (pintype "bidirectional"))
    )
    (net (code "85") (name "unconnected-(PCB1-~{CE}{slash}GPIO07-Pad26)") (class "Default")
      (node (ref "PCB1") (pin "26") (pinfunction "~{CE}/GPIO07_26") (pintype "bidirectional"))
    )
  )
)
